# rf-bm-s02-breakout.net
KiCad netlist of a schematic drawn in EAGLE
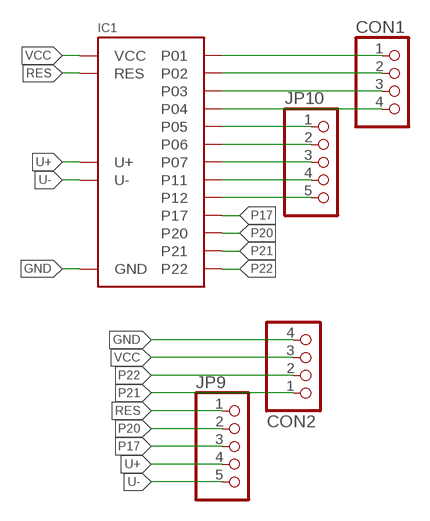
[diagram p0: schematic, sheet 1]

(export (version "E")
  (design (tool "Eeschema 10.0.6"))
  (components
    (comp (ref "CON1")
      (value "GENERIC-1X4STRAIGHT")
      (footprint "eagle-import:PINHEADER-100MIL-1X4-NOSILK")
      (libsource (lib "eagle-import") (part "GENERIC-1X4STRAIGHT"))
    )
    (comp (ref "CON2")
      (value "GENERIC-1X4STRAIGHT")
      (footprint "eagle-import:PINHEADER-100MIL-1X4-NOSILK")
      (libsource (lib "eagle-import") (part "GENERIC-1X4STRAIGHT"))
    )
    (comp (ref "IC1")
      (value "BLUETOOTH-RF-BM-S02")
      (footprint "eagle-import:BLUETOOTH-RF-BM-S02-SMD")
      (libsource (lib "eagle-import") (part "BLUETOOTH-RF-BM-S02"))
    )
    (comp (ref "JP9")
      (value "PINHD-1X5")
      (footprint "eagle-import:1X05")
      (libsource (lib "eagle-import") (part "PINHD-1X5"))
    )
    (comp (ref "JP10")
      (value "PINHD-1X5")
      (footprint "eagle-import:1X05")
      (libsource (lib "eagle-import") (part "PINHD-1X5"))
    )
  )
  (nets
    (net (code "1") (name "GND") (class "Default")
      (node (ref "CON2") (pin "4") (pinfunction "4_4") (pintype "passive"))
      (node (ref "IC1") (pin "P$18") (pinfunction "GND_P$18") (pintype "bidirectional"))
    )
    (net (code "2") (name "Net-(IC1-P01)") (class "Default")
      (node (ref "CON1") (pin "1") (pinfunction "1_1") (pintype "passive"))
      (node (ref "IC1") (pin "P$9") (pinfunction "P01_P$9") (pintype "bidirectional"))
    )
    (net (code "3") (name "Net-(IC1-P02)") (class "Default")
      (node (ref "CON1") (pin "2") (pinfunction "2_2") (pintype "passive"))
      (node (ref "IC1") (pin "P$8") (pinfunction "P02_P$8") (pintype "bidirectional"))
    )
    (net (code "4") (name "Net-(IC1-P03)") (class "Default")
      (node (ref "CON1") (pin "3") (pinfunction "3_3") (pintype "passive"))
      (node (ref "IC1") (pin "P$7") (pinfunction "P03_P$7") (pintype "bidirectional"))
    )
    (net (code "5") (name "Net-(IC1-P04)") (class "Default")
      (node (ref "CON1") (pin "4") (pinfunction "4_4") (pintype "passive"))
      (node (ref "IC1") (pin "P$6") (pinfunction "P04_P$6") (pintype "bidirectional"))
    )
    (net (code "6") (name "Net-(IC1-P05)") (class "Default")
      (node (ref "IC1") (pin "P$5") (pinfunction "P05_P$5") (pintype "bidirectional"))
      (node (ref "JP10") (pin "1") (pinfunction "1_1") (pintype "passive"))
    )
    (net (code "7") (name "Net-(IC1-P06)") (class "Default")
      (node (ref "IC1") (pin "P$4") (pinfunction "P06_P$4") (pintype "bidirectional"))
      (node (ref "JP10") (pin "2") (pinfunction "2_2") (pintype "passive"))
    )
    (net (code "8") (name "Net-(IC1-P07)") (class "Default")
      (node (ref "IC1") (pin "P$3") (pinfunction "P07_P$3") (pintype "bidirectional"))
      (node (ref "JP10") (pin "3") (pinfunction "3_3") (pintype "passive"))
    )
    (net (code "9") (name "Net-(IC1-P11)") (class "Default")
      (node (ref "IC1") (pin "P$2") (pinfunction "P11_P$2") (pintype "bidirectional"))
      (node (ref "JP10") (pin "4") (pinfunction "4_4") (pintype "passive"))
    )
    (net (code "10") (name "Net-(IC1-P12)") (class "Default")
      (node (ref "IC1") (pin "P$1") (pinfunction "P12_P$1") (pintype "bidirectional"))
      (node (ref "JP10") (pin "5") (pinfunction "5_5") (pintype "passive"))
    )
    (net (code "11") (name "P17") (class "Default")
      (node (ref "IC1") (pin "P$12") (pinfunction "P17_P$12") (pintype "bidirectional"))
      (node (ref "JP9") (pin "3") (pinfunction "3_3") (pintype "passive"))
    )
    (net (code "12") (name "P20") (class "Default")
      (node (ref "IC1") (pin "P$13") (pinfunction "P20_P$13") (pintype "bidirectional"))
      (node (ref "JP9") (pin "2") (pinfunction "2_2") (pintype "passive"))
    )
    (net (code "13") (name "P21") (class "Default")
      (node (ref "CON2") (pin "1") (pinfunction "1_1") (pintype "passive"))
      (node (ref "IC1") (pin "P$15") (pinfunction "P21_P$15") (pintype "bidirectional"))
    )
    (net (code "14") (name "P22") (class "Default")
      (node (ref "CON2") (pin "2") (pinfunction "2_2") (pintype "passive"))
      (node (ref "IC1") (pin "P$16") (pinfunction "P22_P$16") (pintype "bidirectional"))
    )
    (net (code "15") (name "RES") (class "Default")
      (node (ref "IC1") (pin "P$14") (pinfunction "RES_P$14") (pintype "bidirectional"))
      (node (ref "JP9") (pin "1") (pinfunction "1_1") (pintype "passive"))
    )
    (net (code "16") (name "U+") (class "Default")
      (node (ref "IC1") (pin "P$11") (pinfunction "U+_P$11") (pintype "bidirectional"))
      (node (ref "JP9") (pin "4") (pinfunction "4_4") (pintype "passive"))
    )
    (net (code "17") (name "U-") (class "Default")
      (node (ref "IC1") (pin "P$10") (pinfunction "U-_P$10") (pintype "bidirectional"))
      (node (ref "JP9") (pin "5") (pinfunction "5_5") (pintype "passive"))
    )
    (net (code "18") (name "VCC") (class "Default")
      (node (ref "CON2") (pin "3") (pinfunction "3_3") (pintype "passive"))
      (node (ref "IC1") (pin "P$17") (pinfunction "VCC_P$17") (pintype "bidirectional"))
    )
  )
)
